# grideye_breakout_v0.net
KiCad netlist of a schematic drawn in EAGLE
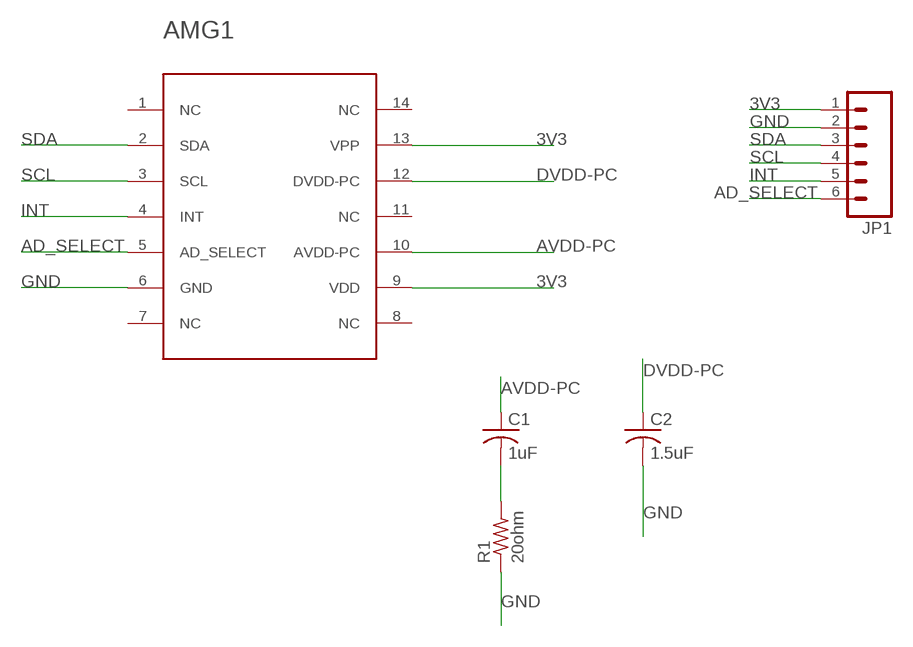
[diagram p0: schematic, sheet 1]

(export (version "E")
  (design (tool "Eeschema 10.0.6"))
  (components
    (comp (ref "AMG1")
      (value "AMG8831")
      (footprint "eagle-import:AMG8831")
      (libsource (lib "eagle-import") (part "AMG8831"))
    )
    (comp (ref "C1")
      (value "1uF")
      (footprint "eagle-import:C0805")
      (libsource (lib "eagle-import") (part "C-USC0805"))
    )
    (comp (ref "C2")
      (value "1.5uF")
      (footprint "eagle-import:C0805")
      (libsource (lib "eagle-import") (part "C-USC0805"))
    )
    (comp (ref "JP1")
      (value "M06LOCK_LONGPADS")
      (footprint "eagle-import:1X06_LOCK_LONGPADS")
      (libsource (lib "eagle-import") (part "M06LOCK_LONGPADS"))
    )
    (comp (ref "R1")
      (value "20ohm")
      (footprint "eagle-import:M0805")
      (libsource (lib "eagle-import") (part "R-US_M0805"))
    )
  )
  (nets
    (net (code "1") (name "/3V3") (class "Default")
      (node (ref "AMG1") (pin "13") (pinfunction "VPP_13") (pintype "power_in"))
      (node (ref "AMG1") (pin "9") (pinfunction "VDD_9") (pintype "power_in"))
      (node (ref "JP1") (pin "1") (pinfunction "1_1") (pintype "passive"))
    )
    (net (code "2") (name "/AD_SELECT") (class "Default")
      (node (ref "AMG1") (pin "5") (pinfunction "AD_SELECT_5") (pintype "bidirectional"))
      (node (ref "JP1") (pin "6") (pinfunction "6_6") (pintype "passive"))
    )
    (net (code "3") (name "/AVDD-PC") (class "Default")
      (node (ref "AMG1") (pin "10") (pinfunction "AVDD-PC_10") (pintype "power_in"))
      (node (ref "C1") (pin "1") (pinfunction "1_1") (pintype "passive"))
    )
    (net (code "4") (name "/DVDD-PC") (class "Default")
      (node (ref "AMG1") (pin "12") (pinfunction "DVDD-PC_12") (pintype "power_in"))
      (node (ref "C2") (pin "1") (pinfunction "1_1") (pintype "passive"))
    )
    (net (code "5") (name "/GND") (class "Default")
      (node (ref "AMG1") (pin "6") (pinfunction "GND_6") (pintype "power_in"))
      (node (ref "C2") (pin "2") (pinfunction "2_2") (pintype "passive"))
      (node (ref "JP1") (pin "2") (pinfunction "2_2") (pintype "passive"))
      (node (ref "R1") (pin "1") (pinfunction "1_1") (pintype "passive"))
    )
    (net (code "6") (name "/INT") (class "Default")
      (node (ref "AMG1") (pin "4") (pinfunction "INT_4") (pintype "bidirectional"))
      (node (ref "JP1") (pin "5") (pinfunction "5_5") (pintype "passive"))
    )
    (net (code "7") (name "/SCL") (class "Default")
      (node (ref "AMG1") (pin "3") (pinfunction "SCL_3") (pintype "bidirectional"))
      (node (ref "JP1") (pin "4") (pinfunction "4_4") (pintype "passive"))
    )
    (net (code "8") (name "/SDA") (class "Default")
      (node (ref "AMG1") (pin "2") (pinfunction "SDA_2") (pintype "bidirectional"))
      (node (ref "JP1") (pin "3") (pinfunction "3_3") (pintype "passive"))
    )
    (net (code "9") (name "Net-(C1-Pad2)") (class "Default")
      (node (ref "C1") (pin "2") (pinfunction "2_2") (pintype "passive"))
      (node (ref "R1") (pin "2") (pinfunction "2_2") (pintype "passive"))
    )
    (net (code "10") (name "unconnected-(AMG1-NC-Pad1)") (class "Default")
      (node (ref "AMG1") (pin "1") (pinfunction "NC_1") (pintype "no_connect"))
    )
    (net (code "11") (name "unconnected-(AMG1-NC-Pad7)") (class "Default")
      (node (ref "AMG1") (pin "7") (pinfunction "NC_7") (pintype "no_connect"))
    )
    (net (code "12") (name "unconnected-(AMG1-NC-Pad8)") (class "Default")
      (node (ref "AMG1") (pin "8") (pinfunction "NC_8") (pintype "no_connect"))
    )
    (net (code "13") (name "unconnected-(AMG1-NC-Pad11)") (class "Default")
      (node (ref "AMG1") (pin "11") (pinfunction "NC_11") (pintype "no_connect"))
    )
    (net (code "14") (name "unconnected-(AMG1-NC-Pad14)") (class "Default")
      (node (ref "AMG1") (pin "14") (pinfunction "NC_14") (pintype "no_connect"))
    )
  )
)
